# SDW_BLUEPILL.net
KiCad netlist of a schematic drawn in EAGLE
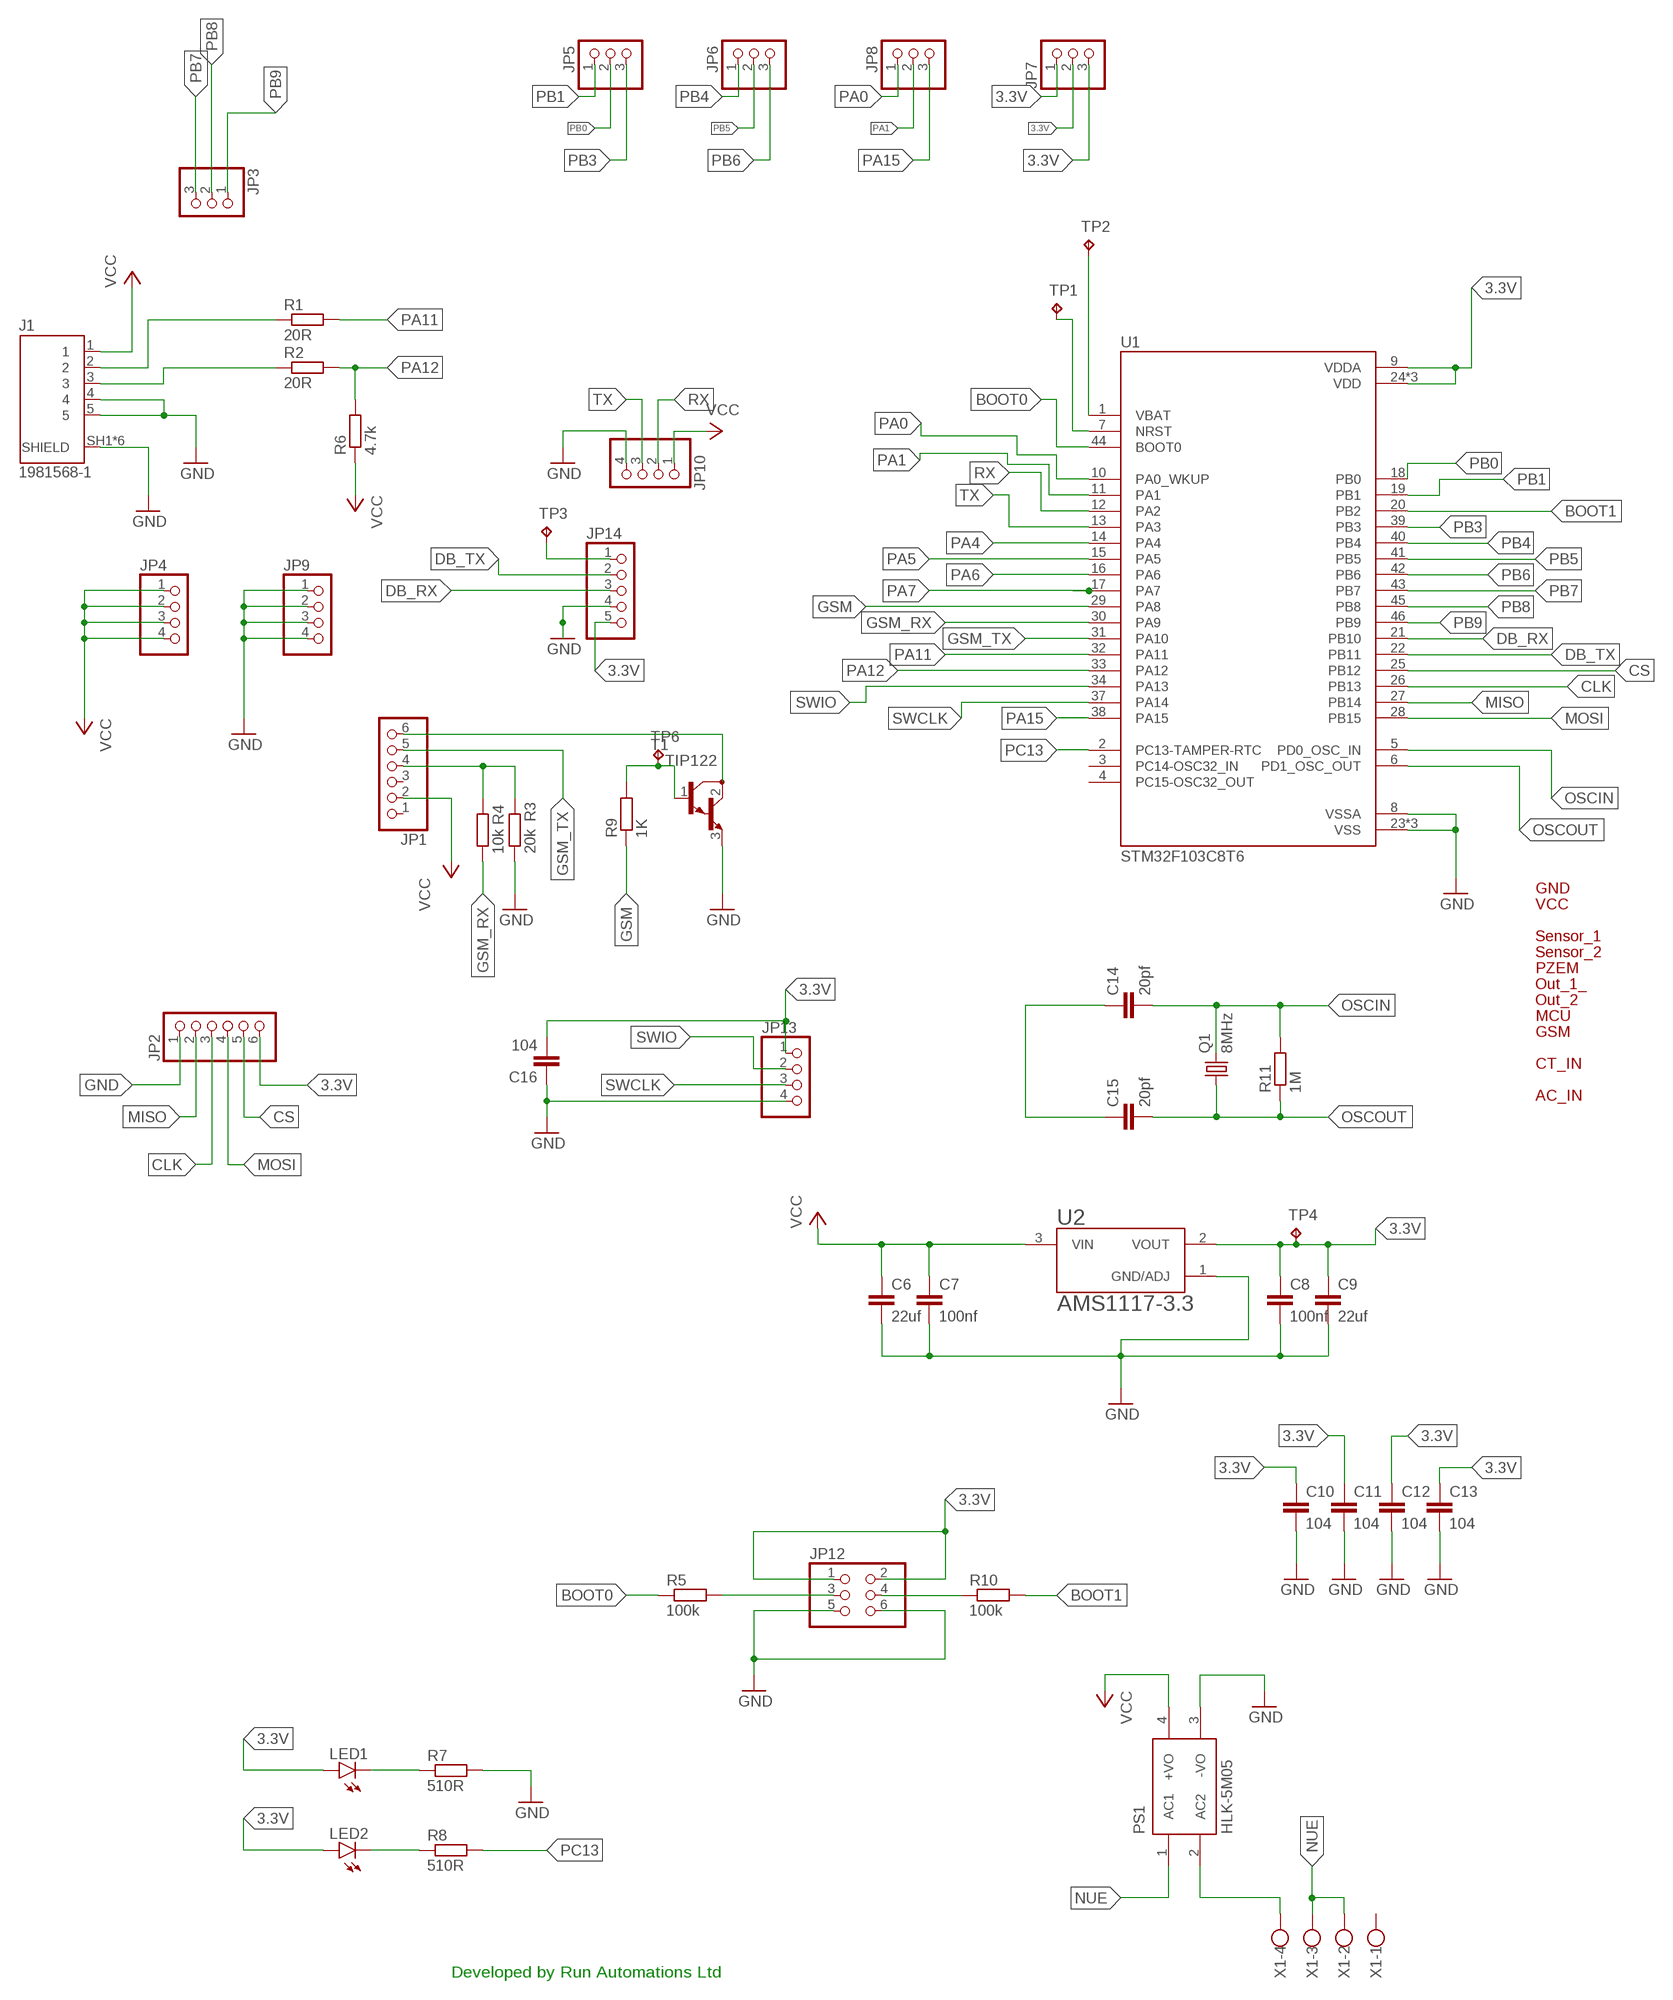
[diagram p0: schematic, sheet 1]

(export (version "E")
  (design (tool "Eeschema 10.0.6"))
  (components
    (comp (ref "C6")
      (value "22uf")
      (footprint "eagle-import:C0805")
      (libsource (lib "eagle-import") (part "C-EUC0805"))
    )
    (comp (ref "C7")
      (value "100nf")
      (footprint "eagle-import:C0805")
      (libsource (lib "eagle-import") (part "C-EUC0805"))
    )
    (comp (ref "C8")
      (value "100nf")
      (footprint "eagle-import:C0805")
      (libsource (lib "eagle-import") (part "C-EUC0805"))
    )
    (comp (ref "C9")
      (value "22uf")
      (footprint "eagle-import:C0805")
      (libsource (lib "eagle-import") (part "C-EUC0805"))
    )
    (comp (ref "C10")
      (value "104")
      (footprint "eagle-import:C0805")
      (libsource (lib "eagle-import") (part "C-EUC0805"))
    )
    (comp (ref "C11")
      (value "104")
      (footprint "eagle-import:C0805")
      (libsource (lib "eagle-import") (part "C-EUC0805"))
    )
    (comp (ref "C12")
      (value "104")
      (footprint "eagle-import:C0805")
      (libsource (lib "eagle-import") (part "C-EUC0805"))
    )
    (comp (ref "C13")
      (value "104")
      (footprint "eagle-import:C0805")
      (libsource (lib "eagle-import") (part "C-EUC0805"))
    )
    (comp (ref "C14")
      (value "20pf")
      (footprint "eagle-import:C0805")
      (libsource (lib "eagle-import") (part "C-EUC0805"))
    )
    (comp (ref "C15")
      (value "20pf")
      (footprint "eagle-import:C0805")
      (libsource (lib "eagle-import") (part "C-EUC0805"))
    )
    (comp (ref "C16")
      (value "104")
      (footprint "eagle-import:C0805")
      (libsource (lib "eagle-import") (part "C-EUC0805"))
    )
    (comp (ref "J1")
      (value "1981568-1")
      (footprint "eagle-import:TE_1981568-1")
      (fields (field (name "MF") "TE Connectivity"))
      (libsource (lib "eagle-import") (part "1981568-1"))
    )
    (comp (ref "JP1")
      (value "PINHD-1X6")
      (footprint "eagle-import:1X06")
      (libsource (lib "eagle-import") (part "PINHD-1X6"))
    )
    (comp (ref "JP2")
      (value "PINHD-1X6")
      (footprint "eagle-import:1X06")
      (libsource (lib "eagle-import") (part "PINHD-1X6"))
    )
    (comp (ref "JP3")
      (value "PINHD-1X3")
      (footprint "eagle-import:1X03")
      (libsource (lib "eagle-import") (part "PINHD-1X3"))
    )
    (comp (ref "JP4")
      (value "PINHD-1X4")
      (footprint "eagle-import:1X04")
      (libsource (lib "eagle-import") (part "PINHD-1X4"))
    )
    (comp (ref "JP5")
      (value "PINHD-1X3")
      (footprint "eagle-import:1X03")
      (libsource (lib "eagle-import") (part "PINHD-1X3"))
    )
    (comp (ref "JP6")
      (value "PINHD-1X3")
      (footprint "eagle-import:1X03")
      (libsource (lib "eagle-import") (part "PINHD-1X3"))
    )
    (comp (ref "JP7")
      (value "PINHD-1X3")
      (footprint "eagle-import:1X03")
      (libsource (lib "eagle-import") (part "PINHD-1X3"))
    )
    (comp (ref "JP8")
      (value "PINHD-1X3")
      (footprint "eagle-import:1X03")
      (libsource (lib "eagle-import") (part "PINHD-1X3"))
    )
    (comp (ref "JP9")
      (value "PINHD-1X4")
      (footprint "eagle-import:1X04")
      (libsource (lib "eagle-import") (part "PINHD-1X4"))
    )
    (comp (ref "JP10")
      (value "PINHD-1X4")
      (footprint "eagle-import:1X04")
      (libsource (lib "eagle-import") (part "PINHD-1X4"))
    )
    (comp (ref "JP12")
      (value "PINHD-2X3")
      (footprint "eagle-import:2X03")
      (libsource (lib "eagle-import") (part "PINHD-2X3"))
    )
    (comp (ref "JP13")
      (value "PINHD-1X4/90")
      (footprint "eagle-import:1X04_90")
      (libsource (lib "eagle-import") (part "PINHD-1X4/90"))
    )
    (comp (ref "JP14")
      (value "PINHD-1X5")
      (footprint "eagle-import:1X05")
      (libsource (lib "eagle-import") (part "PINHD-1X5"))
    )
    (comp (ref "LED1")
      (value "LEDCHIPLED_0805")
      (footprint "eagle-import:CHIPLED_0805")
      (libsource (lib "eagle-import") (part "LEDCHIPLED_0805"))
    )
    (comp (ref "LED2")
      (value "LEDCHIPLED_0805")
      (footprint "eagle-import:CHIPLED_0805")
      (libsource (lib "eagle-import") (part "LEDCHIPLED_0805"))
    )
    (comp (ref "PS1")
      (value "HLK-5M05")
      (footprint "eagle-import:CONV_HLK-5M05")
      (fields (field (name "MF") "Hi-link"))
      (libsource (lib "eagle-import") (part "HLK-5M05"))
    )
    (comp (ref "Q1")
      (value "8MHz")
      (footprint "eagle-import:HC49_S")
      (libsource (lib "eagle-import") (part "CRYSTALHC49S"))
    )
    (comp (ref "R1")
      (value "20R")
      (footprint "eagle-import:M0805")
      (libsource (lib "eagle-import") (part "R-EU_M0805"))
    )
    (comp (ref "R2")
      (value "20R")
      (footprint "eagle-import:M0805")
      (libsource (lib "eagle-import") (part "R-EU_M0805"))
    )
    (comp (ref "R3")
      (value "20k")
      (footprint "eagle-import:M0805")
      (libsource (lib "eagle-import") (part "R-EU_M0805"))
    )
    (comp (ref "R4")
      (value "10k")
      (footprint "eagle-import:M0805")
      (libsource (lib "eagle-import") (part "R-EU_M0805"))
    )
    (comp (ref "R5")
      (value "100k")
      (footprint "eagle-import:M0805")
      (libsource (lib "eagle-import") (part "R-EU_M0805"))
    )
    (comp (ref "R6")
      (value "4.7k")
      (footprint "eagle-import:M0805")
      (libsource (lib "eagle-import") (part "R-EU_M0805"))
    )
    (comp (ref "R7")
      (value "510R")
      (footprint "eagle-import:M0805")
      (libsource (lib "eagle-import") (part "R-EU_M0805"))
    )
    (comp (ref "R8")
      (value "510R")
      (footprint "eagle-import:M0805")
      (libsource (lib "eagle-import") (part "R-EU_M0805"))
    )
    (comp (ref "R9")
      (value "1K")
      (footprint "eagle-import:M0805")
      (libsource (lib "eagle-import") (part "R-EU_M0805"))
    )
    (comp (ref "R10")
      (value "100k")
      (footprint "eagle-import:M0805")
      (libsource (lib "eagle-import") (part "R-EU_M0805"))
    )
    (comp (ref "R11")
      (value "1M")
      (footprint "eagle-import:M0805")
      (libsource (lib "eagle-import") (part "R-EU_M0805"))
    )
    (comp (ref "T1")
      (value "TIP122")
      (footprint "eagle-import:TO220")
      (fields (field (name "MF") "STMicroelectronics"))
      (libsource (lib "eagle-import") (part "TIP122"))
    )
    (comp (ref "TP1")
      (value "TPB1,27")
      (footprint "eagle-import:B1,27")
      (libsource (lib "eagle-import") (part "TPB1,27"))
    )
    (comp (ref "TP2")
      (value "TPB1,27")
      (footprint "eagle-import:B1,27")
      (libsource (lib "eagle-import") (part "TPB1,27"))
    )
    (comp (ref "TP3")
      (value "TPB1,27")
      (footprint "eagle-import:B1,27")
      (libsource (lib "eagle-import") (part "TPB1,27"))
    )
    (comp (ref "TP4")
      (value "TPB1,27")
      (footprint "eagle-import:B1,27")
      (libsource (lib "eagle-import") (part "TPB1,27"))
    )
    (comp (ref "TP6")
      (value "TPB1,27")
      (footprint "eagle-import:B1,27")
      (libsource (lib "eagle-import") (part "TPB1,27"))
    )
    (comp (ref "U$2")
      (value "VCC0")
      (footprint "eagle-import:VCC0")
      (libsource (lib "eagle-import") (part "VCC0"))
    )
    (comp (ref "U$3")
      (value "GND0")
      (footprint "eagle-import:GND0")
      (libsource (lib "eagle-import") (part "GND0"))
    )
    (comp (ref "U$5")
      (value "SENSOR_10")
      (footprint "eagle-import:SENSOR_10")
      (libsource (lib "eagle-import") (part "SENSOR_10"))
    )
    (comp (ref "U$6")
      (value "SENSOR_20")
      (footprint "eagle-import:SENSOR_20")
      (libsource (lib "eagle-import") (part "SENSOR_20"))
    )
    (comp (ref "U$7")
      (value "PZEM0")
      (footprint "eagle-import:PZEM0")
      (libsource (lib "eagle-import") (part "PZEM0"))
    )
    (comp (ref "U$8")
      (value "OUT_1_0")
      (footprint "eagle-import:OUT_1_0")
      (libsource (lib "eagle-import") (part "OUT_1_0"))
    )
    (comp (ref "U$9")
      (value "OUT_20")
      (footprint "eagle-import:OUT_20")
      (libsource (lib "eagle-import") (part "OUT_20"))
    )
    (comp (ref "U$10")
      (value "MCU0")
      (footprint "eagle-import:MCU0")
      (libsource (lib "eagle-import") (part "MCU0"))
    )
    (comp (ref "U$11")
      (value "GSM0")
      (footprint "eagle-import:GSM0")
      (libsource (lib "eagle-import") (part "GSM0"))
    )
    (comp (ref "U$13")
      (value "CT_IN0")
      (footprint "eagle-import:CT_IN0")
      (libsource (lib "eagle-import") (part "CT_IN0"))
    )
    (comp (ref "U$15")
      (value "AC_IN0")
      (footprint "eagle-import:AC_IN0")
      (libsource (lib "eagle-import") (part "AC_IN0"))
    )
    (comp (ref "U1")
      (value "STM32F103C8T6")
      (footprint "eagle-import:QFP50P900X900X160-48N")
      (fields (field (name "MF") "STMicroelectronics"))
      (libsource (lib "eagle-import") (part "STM32F103C8T6"))
    )
    (comp (ref "U2")
      (value "AMS1117-3.3")
      (footprint "eagle-import:SOT229P700X180-4N")
      (fields (field (name "MF") "Advanced Monolithic Systems"))
      (libsource (lib "eagle-import") (part "AMS1117-3.3"))
    )
    (comp (ref "X1")
      (value "W237-4")
      (footprint "eagle-import:W237-4")
      (libsource (lib "eagle-import") (part "W237-4"))
    )
  )
  (nets
    (net (code "1") (name "3.3V") (class "Default")
      (node (ref "C10") (pin "1") (pinfunction "1_1") (pintype "passive"))
      (node (ref "C11") (pin "1") (pinfunction "1_1") (pintype "passive"))
      (node (ref "C12") (pin "1") (pinfunction "1_1") (pintype "passive"))
      (node (ref "C13") (pin "1") (pinfunction "1_1") (pintype "passive"))
      (node (ref "C16") (pin "2") (pinfunction "2_2") (pintype "passive"))
      (node (ref "C8") (pin "1") (pinfunction "1_1") (pintype "passive"))
      (node (ref "C9") (pin "1") (pinfunction "1_1") (pintype "passive"))
      (node (ref "JP12") (pin "1") (pinfunction "1_1") (pintype "passive"))
      (node (ref "JP12") (pin "2") (pinfunction "2_2") (pintype "passive"))
      (node (ref "JP13") (pin "1") (pinfunction "1_1") (pintype "passive"))
      (node (ref "JP14") (pin "5") (pinfunction "5_5") (pintype "passive"))
      (node (ref "JP2") (pin "6") (pinfunction "6_6") (pintype "passive"))
      (node (ref "JP7") (pin "1") (pinfunction "1_1") (pintype "passive"))
      (node (ref "JP7") (pin "2") (pinfunction "2_2") (pintype "passive"))
      (node (ref "JP7") (pin "3") (pinfunction "3_3") (pintype "passive"))
      (node (ref "LED1") (pin "A") (pinfunction "A_A") (pintype "passive"))
      (node (ref "LED2") (pin "A") (pinfunction "A_A") (pintype "passive"))
      (node (ref "TP4") (pin "TP") (pinfunction "TP_TP") (pintype "input"))
      (node (ref "U1") (pin "24") (pinfunction "VDD_24") (pintype "power_in"))
      (node (ref "U1") (pin "36") (pinfunction "VDD_36") (pintype "power_in"))
      (node (ref "U1") (pin "48") (pinfunction "VDD_48") (pintype "power_in"))
      (node (ref "U1") (pin "9") (pinfunction "VDDA_9") (pintype "power_in"))
      (node (ref "U2") (pin "2") (pinfunction "VOUT_2") (pintype "output"))
    )
    (net (code "2") (name "BOOT0") (class "Default")
      (node (ref "R5") (pin "1") (pinfunction "1_1") (pintype "passive"))
      (node (ref "U1") (pin "44") (pinfunction "BOOT0_44") (pintype "input"))
    )
    (net (code "3") (name "BOOT1") (class "Default")
      (node (ref "R10") (pin "2") (pinfunction "2_2") (pintype "passive"))
      (node (ref "U1") (pin "20") (pinfunction "PB2_20") (pintype "bidirectional"))
    )
    (net (code "4") (name "CLK") (class "Default")
      (node (ref "JP2") (pin "3") (pinfunction "3_3") (pintype "passive"))
      (node (ref "U1") (pin "26") (pinfunction "PB13_26") (pintype "bidirectional"))
    )
    (net (code "5") (name "CS") (class "Default")
      (node (ref "JP2") (pin "5") (pinfunction "5_5") (pintype "passive"))
      (node (ref "U1") (pin "25") (pinfunction "PB12_25") (pintype "bidirectional"))
    )
    (net (code "6") (name "DB_RX") (class "Default")
      (node (ref "JP14") (pin "3") (pinfunction "3_3") (pintype "passive"))
      (node (ref "U1") (pin "21") (pinfunction "PB10_21") (pintype "bidirectional"))
    )
    (net (code "7") (name "DB_TX") (class "Default")
      (node (ref "JP14") (pin "2") (pinfunction "2_2") (pintype "passive"))
      (node (ref "U1") (pin "22") (pinfunction "PB11_22") (pintype "bidirectional"))
    )
    (net (code "8") (name "GND") (class "Default")
      (node (ref "C10") (pin "2") (pinfunction "2_2") (pintype "passive"))
      (node (ref "C11") (pin "2") (pinfunction "2_2") (pintype "passive"))
      (node (ref "C12") (pin "2") (pinfunction "2_2") (pintype "passive"))
      (node (ref "C13") (pin "2") (pinfunction "2_2") (pintype "passive"))
      (node (ref "C16") (pin "1") (pinfunction "1_1") (pintype "passive"))
      (node (ref "C6") (pin "2") (pinfunction "2_2") (pintype "passive"))
      (node (ref "C7") (pin "2") (pinfunction "2_2") (pintype "passive"))
      (node (ref "C8") (pin "2") (pinfunction "2_2") (pintype "passive"))
      (node (ref "C9") (pin "2") (pinfunction "2_2") (pintype "passive"))
      (node (ref "J1") (pin "4") (pinfunction "4_4") (pintype "passive"))
      (node (ref "J1") (pin "5") (pinfunction "5_5") (pintype "passive"))
      (node (ref "J1") (pin "SH1") (pinfunction "SHIELD_SH1") (pintype "passive"))
      (node (ref "J1") (pin "SH2") (pinfunction "SHIELD_SH2") (pintype "passive"))
      (node (ref "J1") (pin "SH3") (pinfunction "SHIELD_SH3") (pintype "passive"))
      (node (ref "J1") (pin "SH4") (pinfunction "SHIELD_SH4") (pintype "passive"))
      (node (ref "J1") (pin "SH5") (pinfunction "SHIELD_SH5") (pintype "passive"))
      (node (ref "J1") (pin "SH6") (pinfunction "SHIELD_SH6") (pintype "passive"))
      (node (ref "JP10") (pin "4") (pinfunction "4_4") (pintype "passive"))
      (node (ref "JP12") (pin "5") (pinfunction "5_5") (pintype "passive"))
      (node (ref "JP12") (pin "6") (pinfunction "6_6") (pintype "passive"))
      (node (ref "JP13") (pin "4") (pinfunction "4_4") (pintype "passive"))
      (node (ref "JP14") (pin "4") (pinfunction "4_4") (pintype "passive"))
      (node (ref "JP2") (pin "1") (pinfunction "1_1") (pintype "passive"))
      (node (ref "JP9") (pin "1") (pinfunction "1_1") (pintype "passive"))
      (node (ref "JP9") (pin "2") (pinfunction "2_2") (pintype "passive"))
      (node (ref "JP9") (pin "3") (pinfunction "3_3") (pintype "passive"))
      (node (ref "JP9") (pin "4") (pinfunction "4_4") (pintype "passive"))
      (node (ref "PS1") (pin "3") (pinfunction "-VO_3") (pintype "output"))
      (node (ref "R3") (pin "1") (pinfunction "1_1") (pintype "passive"))
      (node (ref "R7") (pin "2") (pinfunction "2_2") (pintype "passive"))
      (node (ref "T1") (pin "3") (pinfunction "E_3") (pintype "passive"))
      (node (ref "U1") (pin "23") (pinfunction "VSS_23") (pintype "power_in"))
      (node (ref "U1") (pin "35") (pinfunction "VSS_35") (pintype "power_in"))
      (node (ref "U1") (pin "47") (pinfunction "VSS_47") (pintype "power_in"))
      (node (ref "U1") (pin "8") (pinfunction "VSSA_8") (pintype "power_in"))
      (node (ref "U2") (pin "1") (pinfunction "GND/ADJ_1") (pintype "power_in"))
    )
    (net (code "9") (name "GSM") (class "Default")
      (node (ref "R9") (pin "1") (pinfunction "1_1") (pintype "passive"))
      (node (ref "U1") (pin "29") (pinfunction "PA8_29") (pintype "bidirectional"))
    )
    (net (code "10") (name "GSM_RX") (class "Default")
      (node (ref "R4") (pin "1") (pinfunction "1_1") (pintype "passive"))
      (node (ref "U1") (pin "30") (pinfunction "PA9_30") (pintype "bidirectional"))
    )
    (net (code "11") (name "GSM_TX") (class "Default")
      (node (ref "JP1") (pin "5") (pinfunction "5_5") (pintype "passive"))
      (node (ref "U1") (pin "31") (pinfunction "PA10_31") (pintype "bidirectional"))
    )
    (net (code "12") (name "MISO") (class "Default")
      (node (ref "JP2") (pin "2") (pinfunction "2_2") (pintype "passive"))
      (node (ref "U1") (pin "27") (pinfunction "PB14_27") (pintype "bidirectional"))
    )
    (net (code "13") (name "MOSI") (class "Default")
      (node (ref "JP2") (pin "4") (pinfunction "4_4") (pintype "passive"))
      (node (ref "U1") (pin "28") (pinfunction "PB15_28") (pintype "bidirectional"))
    )
    (net (code "14") (name "NUE") (class "Default")
      (node (ref "PS1") (pin "1") (pinfunction "AC1_1") (pintype "input"))
      (node (ref "X1") (pin "2") (pinfunction "KL_2") (pintype "passive"))
      (node (ref "X1") (pin "3") (pinfunction "KL_3") (pintype "passive"))
    )
    (net (code "15") (name "Net-(C14-Pad1)") (class "Default")
      (node (ref "C14") (pin "1") (pinfunction "1_1") (pintype "passive"))
      (node (ref "C15") (pin "1") (pinfunction "1_1") (pintype "passive"))
    )
    (net (code "16") (name "Net-(J1-Pad2)") (class "Default")
      (node (ref "J1") (pin "2") (pinfunction "2_2") (pintype "passive"))
      (node (ref "R1") (pin "1") (pinfunction "1_1") (pintype "passive"))
    )
    (net (code "17") (name "Net-(J1-Pad3)") (class "Default")
      (node (ref "J1") (pin "3") (pinfunction "3_3") (pintype "passive"))
      (node (ref "R2") (pin "1") (pinfunction "1_1") (pintype "passive"))
    )
    (net (code "18") (name "Net-(JP1-Pad4)") (class "Default")
      (node (ref "JP1") (pin "4") (pinfunction "4_4") (pintype "passive"))
      (node (ref "R3") (pin "2") (pinfunction "2_2") (pintype "passive"))
      (node (ref "R4") (pin "2") (pinfunction "2_2") (pintype "passive"))
    )
    (net (code "19") (name "Net-(JP12-Pad3)") (class "Default")
      (node (ref "JP12") (pin "3") (pinfunction "3_3") (pintype "passive"))
      (node (ref "R5") (pin "2") (pinfunction "2_2") (pintype "passive"))
    )
    (net (code "20") (name "Net-(JP12-Pad4)") (class "Default")
      (node (ref "JP12") (pin "4") (pinfunction "4_4") (pintype "passive"))
      (node (ref "R10") (pin "1") (pinfunction "1_1") (pintype "passive"))
    )
    (net (code "21") (name "Net-(JP14-Pad1)") (class "Default")
      (node (ref "JP14") (pin "1") (pinfunction "1_1") (pintype "passive"))
      (node (ref "TP3") (pin "TP") (pinfunction "TP_TP") (pintype "input"))
    )
    (net (code "22") (name "Net-(LED1-PadC)") (class "Default")
      (node (ref "LED1") (pin "C") (pinfunction "C_C") (pintype "passive"))
      (node (ref "R7") (pin "1") (pinfunction "1_1") (pintype "passive"))
    )
    (net (code "23") (name "Net-(LED2-PadC)") (class "Default")
      (node (ref "LED2") (pin "C") (pinfunction "C_C") (pintype "passive"))
      (node (ref "R8") (pin "1") (pinfunction "1_1") (pintype "passive"))
    )
    (net (code "24") (name "Net-(PS1-AC2)") (class "Default")
      (node (ref "PS1") (pin "2") (pinfunction "AC2_2") (pintype "input"))
      (node (ref "X1") (pin "4") (pinfunction "KL_4") (pintype "passive"))
    )
    (net (code "25") (name "Net-(T1-B)") (class "Default")
      (node (ref "R9") (pin "2") (pinfunction "2_2") (pintype "passive"))
      (node (ref "T1") (pin "1") (pinfunction "B_1") (pintype "passive"))
      (node (ref "TP6") (pin "TP") (pinfunction "TP_TP") (pintype "input"))
    )
    (net (code "26") (name "Net-(T1-C)") (class "Default")
      (node (ref "JP1") (pin "6") (pinfunction "6_6") (pintype "passive"))
      (node (ref "T1") (pin "2") (pinfunction "C_2") (pintype "passive"))
    )
    (net (code "27") (name "Net-(U1-NRST)") (class "Default")
      (node (ref "TP1") (pin "TP") (pinfunction "TP_TP") (pintype "input"))
      (node (ref "U1") (pin "7") (pinfunction "NRST_7") (pintype "input"))
    )
    (net (code "28") (name "Net-(U1-VBAT)") (class "Default")
      (node (ref "TP2") (pin "TP") (pinfunction "TP_TP") (pintype "input"))
      (node (ref "U1") (pin "1") (pinfunction "VBAT_1") (pintype "bidirectional"))
    )
    (net (code "29") (name "OSCIN") (class "Default")
      (node (ref "C14") (pin "2") (pinfunction "2_2") (pintype "passive"))
      (node (ref "Q1") (pin "2") (pinfunction "2_2") (pintype "passive"))
      (node (ref "R11") (pin "2") (pinfunction "2_2") (pintype "passive"))
      (node (ref "U1") (pin "5") (pinfunction "PD0_OSC_IN_5") (pintype "bidirectional"))
    )
    (net (code "30") (name "OSCOUT") (class "Default")
      (node (ref "C15") (pin "2") (pinfunction "2_2") (pintype "passive"))
      (node (ref "Q1") (pin "1") (pinfunction "1_1") (pintype "passive"))
      (node (ref "R11") (pin "1") (pinfunction "1_1") (pintype "passive"))
      (node (ref "U1") (pin "6") (pinfunction "PD1_OSC_OUT_6") (pintype "bidirectional"))
    )
    (net (code "31") (name "PA0") (class "Default")
      (node (ref "JP8") (pin "1") (pinfunction "1_1") (pintype "passive"))
      (node (ref "U1") (pin "10") (pinfunction "PA0_WKUP_10") (pintype "bidirectional"))
    )
    (net (code "32") (name "PA1") (class "Default")
      (node (ref "JP8") (pin "2") (pinfunction "2_2") (pintype "passive"))
      (node (ref "U1") (pin "11") (pinfunction "PA1_11") (pintype "bidirectional"))
    )
    (net (code "33") (name "PA4") (class "Default")
      (node (ref "U1") (pin "14") (pinfunction "PA4_14") (pintype "bidirectional"))
    )
    (net (code "34") (name "PA5") (class "Default")
      (node (ref "U1") (pin "15") (pinfunction "PA5_15") (pintype "bidirectional"))
    )
    (net (code "35") (name "PA6") (class "Default")
      (node (ref "U1") (pin "16") (pinfunction "PA6_16") (pintype "bidirectional"))
    )
    (net (code "36") (name "PA7") (class "Default")
      (node (ref "U1") (pin "17") (pinfunction "PA7_17") (pintype "bidirectional"))
    )
    (net (code "37") (name "PA11") (class "Default")
      (node (ref "R1") (pin "2") (pinfunction "2_2") (pintype "passive"))
      (node (ref "U1") (pin "32") (pinfunction "PA11_32") (pintype "bidirectional"))
    )
    (net (code "38") (name "PA12") (class "Default")
      (node (ref "R2") (pin "2") (pinfunction "2_2") (pintype "passive"))
      (node (ref "R6") (pin "2") (pinfunction "2_2") (pintype "passive"))
      (node (ref "U1") (pin "33") (pinfunction "PA12_33") (pintype "bidirectional"))
    )
    (net (code "39") (name "PA15") (class "Default")
      (node (ref "JP8") (pin "3") (pinfunction "3_3") (pintype "passive"))
      (node (ref "U1") (pin "38") (pinfunction "PA15_38") (pintype "bidirectional"))
    )
    (net (code "40") (name "PB0") (class "Default")
      (node (ref "JP5") (pin "2") (pinfunction "2_2") (pintype "passive"))
      (node (ref "U1") (pin "18") (pinfunction "PB0_18") (pintype "bidirectional"))
    )
    (net (code "41") (name "PB1") (class "Default")
      (node (ref "JP5") (pin "1") (pinfunction "1_1") (pintype "passive"))
      (node (ref "U1") (pin "19") (pinfunction "PB1_19") (pintype "bidirectional"))
    )
    (net (code "42") (name "PB3") (class "Default")
      (node (ref "JP5") (pin "3") (pinfunction "3_3") (pintype "passive"))
      (node (ref "U1") (pin "39") (pinfunction "PB3_39") (pintype "bidirectional"))
    )
    (net (code "43") (name "PB4") (class "Default")
      (node (ref "JP6") (pin "1") (pinfunction "1_1") (pintype "passive"))
      (node (ref "U1") (pin "40") (pinfunction "PB4_40") (pintype "bidirectional"))
    )
    (net (code "44") (name "PB5") (class "Default")
      (node (ref "JP6") (pin "2") (pinfunction "2_2") (pintype "passive"))
      (node (ref "U1") (pin "41") (pinfunction "PB5_41") (pintype "bidirectional"))
    )
    (net (code "45") (name "PB6") (class "Default")
      (node (ref "JP6") (pin "3") (pinfunction "3_3") (pintype "passive"))
      (node (ref "U1") (pin "42") (pinfunction "PB6_42") (pintype "bidirectional"))
    )
    (net (code "46") (name "PB7") (class "Default")
      (node (ref "JP3") (pin "3") (pinfunction "3_3") (pintype "passive"))
      (node (ref "U1") (pin "43") (pinfunction "PB7_43") (pintype "bidirectional"))
    )
    (net (code "47") (name "PB8") (class "Default")
      (node (ref "JP3") (pin "2") (pinfunction "2_2") (pintype "passive"))
      (node (ref "U1") (pin "45") (pinfunction "PB8_45") (pintype "bidirectional"))
    )
    (net (code "48") (name "PB9") (class "Default")
      (node (ref "JP3") (pin "1") (pinfunction "1_1") (pintype "passive"))
      (node (ref "U1") (pin "46") (pinfunction "PB9_46") (pintype "bidirectional"))
    )
    (net (code "49") (name "PC13") (class "Default")
      (node (ref "R8") (pin "2") (pinfunction "2_2") (pintype "passive"))
      (node (ref "U1") (pin "2") (pinfunction "PC13-TAMPER-RTC_2") (pintype "bidirectional"))
    )
    (net (code "50") (name "RX") (class "Default")
      (node (ref "JP10") (pin "2") (pinfunction "2_2") (pintype "passive"))
      (node (ref "U1") (pin "12") (pinfunction "PA2_12") (pintype "bidirectional"))
    )
    (net (code "51") (name "SWCLK") (class "Default")
      (node (ref "JP13") (pin "3") (pinfunction "3_3") (pintype "passive"))
      (node (ref "U1") (pin "37") (pinfunction "PA14_37") (pintype "bidirectional"))
    )
    (net (code "52") (name "SWIO") (class "Default")
      (node (ref "JP13") (pin "2") (pinfunction "2_2") (pintype "passive"))
      (node (ref "U1") (pin "34") (pinfunction "PA13_34") (pintype "bidirectional"))
    )
    (net (code "53") (name "TX") (class "Default")
      (node (ref "JP10") (pin "3") (pinfunction "3_3") (pintype "passive"))
      (node (ref "U1") (pin "13") (pinfunction "PA3_13") (pintype "bidirectional"))
    )
    (net (code "54") (name "VCC") (class "Default")
      (node (ref "C6") (pin "1") (pinfunction "1_1") (pintype "passive"))
      (node (ref "C7") (pin "1") (pinfunction "1_1") (pintype "passive"))
      (node (ref "J1") (pin "1") (pinfunction "1_1") (pintype "passive"))
      (node (ref "JP1") (pin "2") (pinfunction "2_2") (pintype "passive"))
      (node (ref "JP10") (pin "1") (pinfunction "1_1") (pintype "passive"))
      (node (ref "JP4") (pin "1") (pinfunction "1_1") (pintype "passive"))
      (node (ref "JP4") (pin "2") (pinfunction "2_2") (pintype "passive"))
      (node (ref "JP4") (pin "3") (pinfunction "3_3") (pintype "passive"))
      (node (ref "JP4") (pin "4") (pinfunction "4_4") (pintype "passive"))
      (node (ref "PS1") (pin "4") (pinfunction "+VO_4") (pintype "output"))
      (node (ref "R6") (pin "1") (pinfunction "1_1") (pintype "passive"))
      (node (ref "U2") (pin "3") (pinfunction "VIN_3") (pintype "input"))
    )
    (net (code "55") (name "unconnected-(JP1-Pad1)") (class "Default")
      (node (ref "JP1") (pin "1") (pinfunction "1_1") (pintype "passive"))
    )
    (net (code "56") (name "unconnected-(JP1-Pad3)") (class "Default")
      (node (ref "JP1") (pin "3") (pinfunction "3_3") (pintype "passive"))
    )
    (net (code "57") (name "unconnected-(U1-PC14-OSC32_IN-Pad3)") (class "Default")
      (node (ref "U1") (pin "3") (pinfunction "PC14-OSC32_IN_3") (pintype "bidirectional"))
    )
    (net (code "58") (name "unconnected-(U1-PC15-OSC32_OUT-Pad4)") (class "Default")
      (node (ref "U1") (pin "4") (pinfunction "PC15-OSC32_OUT_4") (pintype "bidirectional"))
    )
    (net (code "59") (name "unconnected-(X1A-KL-Pad1)") (class "Default")
      (node (ref "X1") (pin "1") (pinfunction "KL_1") (pintype "passive"))
    )
  )
)
